# Sheet7.net
KiCad netlist of a schematic drawn in Altium Designer
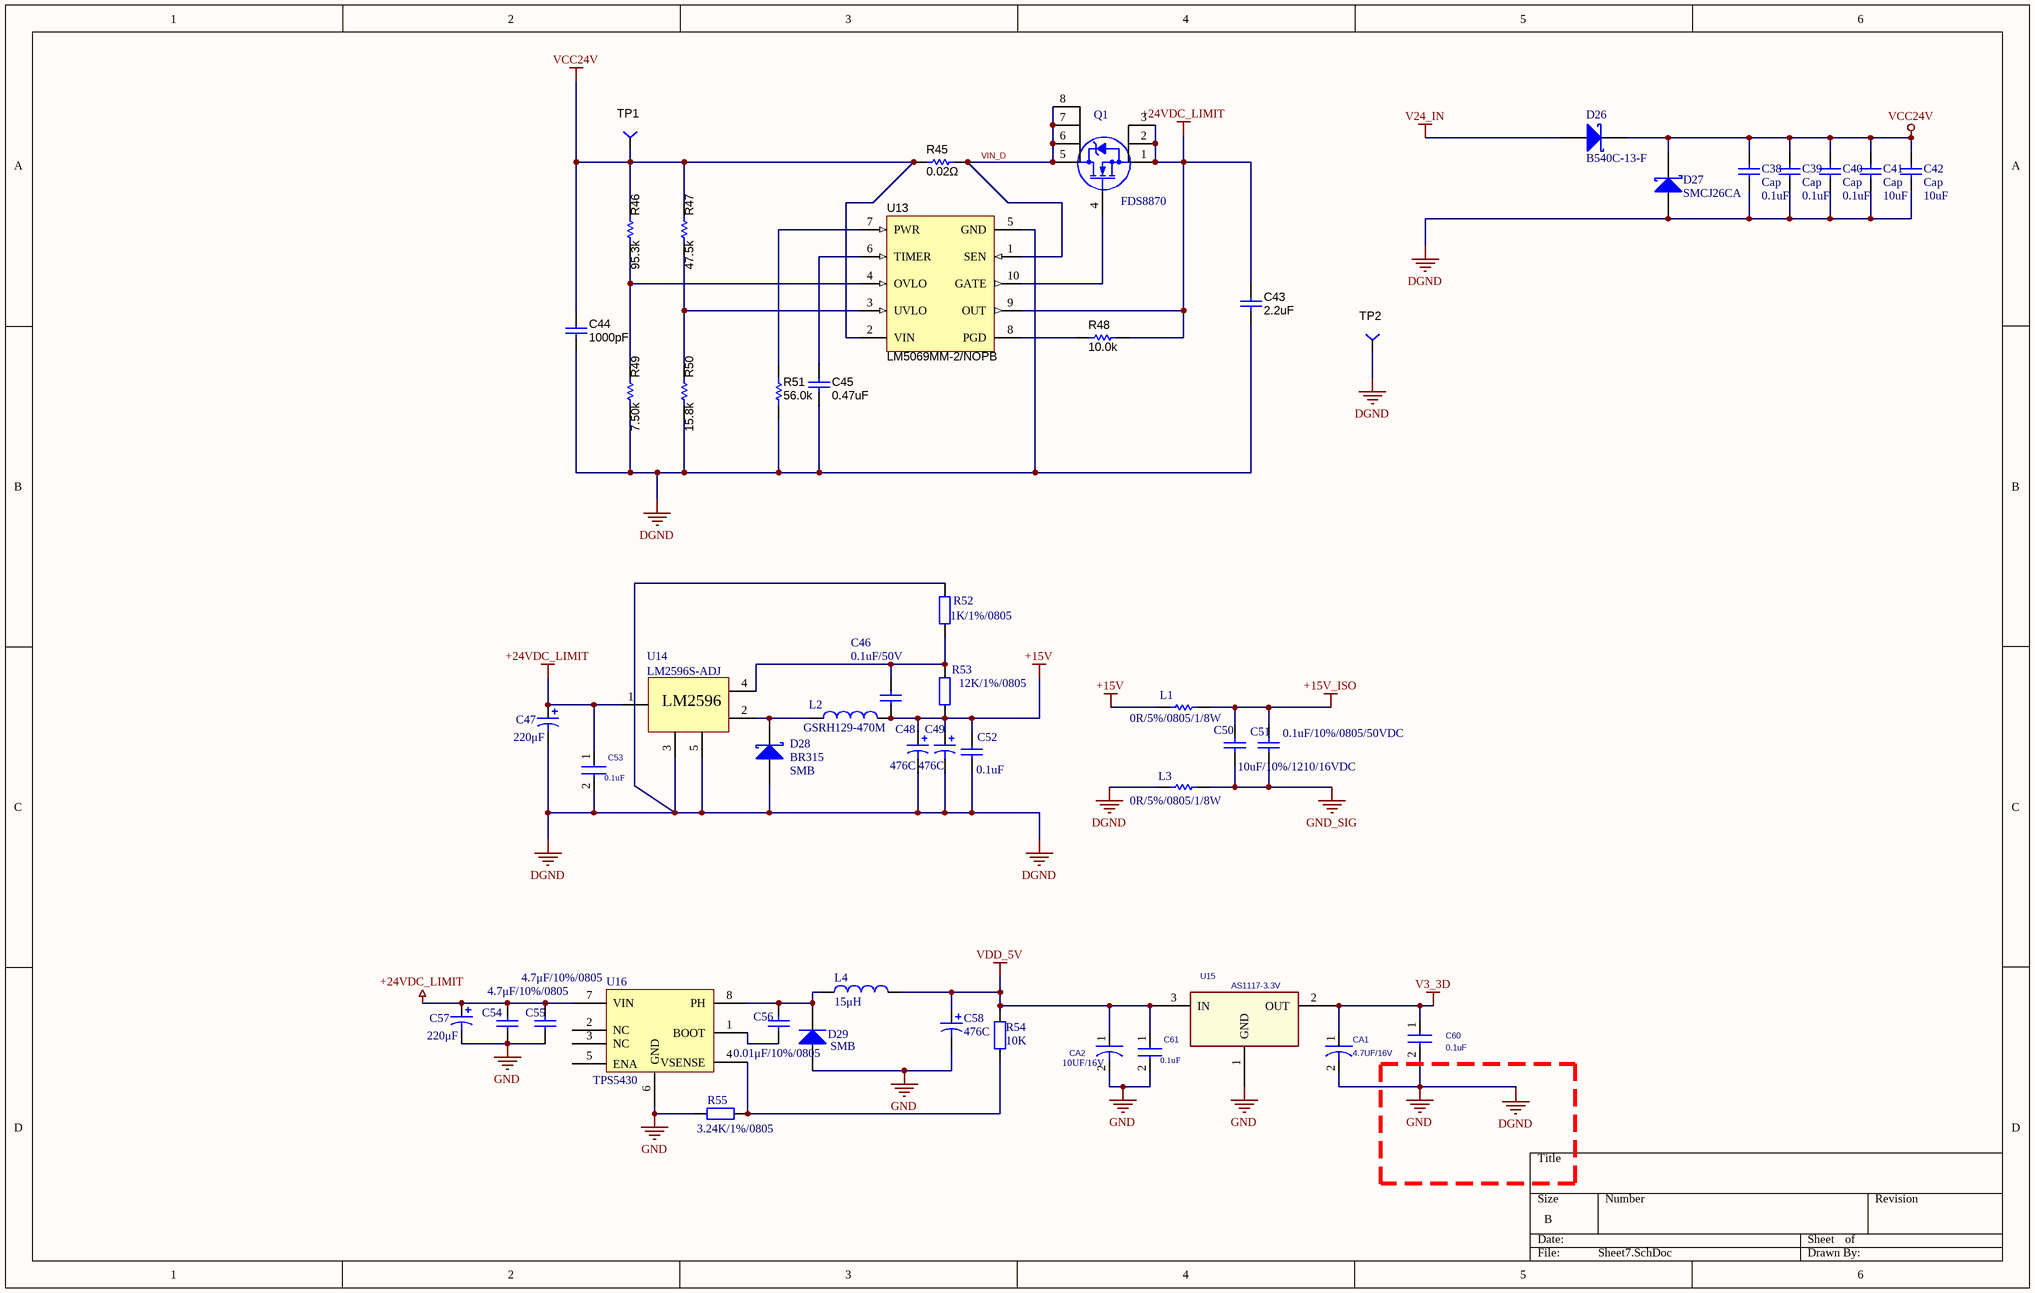
[diagram p0: Sheet7.SchDoc]

(export (version "E")
  (design (tool "Eeschema 10.0.6"))
  (components
    (comp (ref "C38")
      (value "Cap")
      (footprint "0805_cap")
      (description "Capacitor")
      (fields (field (name "ALTIUM_VALUE") "0.1uF") (field (name "PUBLISHER") "Altium Limited"))
      (libsource (lib "Miscellaneous Devices") (part "Cap"))
    )
    (comp (ref "C39")
      (value "Cap")
      (footprint "0805_cap")
      (description "Capacitor")
      (fields (field (name "ALTIUM_VALUE") "0.1uF") (field (name "PUBLISHER") "Altium Limited"))
      (libsource (lib "Miscellaneous Devices") (part "Cap"))
    )
    (comp (ref "C40")
      (value "Cap")
      (footprint "0805_cap")
      (description "Capacitor")
      (fields (field (name "ALTIUM_VALUE") "0.1uF") (field (name "PUBLISHER") "Altium Limited"))
      (libsource (lib "Miscellaneous Devices") (part "Cap"))
    )
    (comp (ref "C41")
      (value "Cap")
      (footprint "0805_cap")
      (description "Capacitor")
      (fields (field (name "ALTIUM_VALUE") "10uF") (field (name "PUBLISHER") "Altium Limited"))
      (libsource (lib "Miscellaneous Devices") (part "Cap"))
    )
    (comp (ref "C42")
      (value "Cap")
      (footprint "0805_cap")
      (description "Capacitor")
      (fields (field (name "ALTIUM_VALUE") "10uF") (field (name "PUBLISHER") "Altium Limited"))
      (libsource (lib "Miscellaneous Devices") (part "Cap"))
    )
    (comp (ref "C43")
      (value "GRM32ER72A225KA35L")
      (footprint "1210")
      (description "CAP, CERM, 2.2uF, 100V, +/-10%, X7R, 1210")
      (fields
        (field (name "VALUEDISPLAYED") "2.2uF")
        (field (name "MANUFACTURER") "MuRata")
        (field (name "PUBLISHER") "Texas Instruments")
      )
      (libsource (lib "Capacitor_Ceramic") (part "GRM32ER72A225KA35L"))
    )
    (comp (ref "C44")
      (value "06031C102JAT2A")
      (footprint "0805_cap")
      (description "CAP, CERM, 1000pF, 100V, +/-5%, X7R, 0603")
      (fields
        (field (name "VALUEDISPLAYED") "1000pF")
        (field (name "MANUFACTURER") "AVX")
        (field (name "PUBLISHER") "Texas Instruments")
      )
      (libsource (lib "Capacitor_Ceramic") (part "06031C102JAT2A"))
    )
    (comp (ref "C45")
      (value "UMK107ABJ474KA-T")
      (footprint "0805_cap")
      (description "CAP, CERM, 0.47uF, 50V, 10%, X5R, 0603")
      (fields
        (field (name "MANUFACTURER") "Taiyo Yuden")
        (field (name "VALUEDISPLAYED") "0.47uF")
        (field (name "PUBLISHER") "Texas Instruments")
      )
      (libsource (lib "TI-INDIA-ALTIUM") (part "UMK107ABJ474KA-T"))
    )
    (comp (ref "C46")
      (value "0.1uF/50V")
      (footprint "C-0805")
      (description "Capacitor")
      (libsource (lib "PCB_Project1_3") (part "Cap"))
    )
    (comp (ref "C47")
      (value "220μF")
      (footprint "CZ3.0/6.5")
      (description "Polarized Capacitor (Radial)")
      (fields (field (name "PUBLISHER") "Altium Limited"))
      (libsource (lib "Miscellaneous Devices") (part "Cap Pol1"))
    )
    (comp (ref "C48")
      (value "476C")
      (footprint "7343-43")
      (description "Polarized Capacitor (Radial)")
      (fields (field (name "PUBLISHER") "Altium Limited"))
      (libsource (lib "Miscellaneous Devices") (part "Cap Pol1"))
    )
    (comp (ref "C49")
      (value "476C")
      (footprint "7343-43")
      (description "Polarized Capacitor (Radial)")
      (fields (field (name "PUBLISHER") "Altium Limited"))
      (libsource (lib "Miscellaneous Devices") (part "Cap Pol1"))
    )
    (comp (ref "C50")
      (value "10uF/10%/1210/16VDC")
      (footprint "C-1210")
      (libsource (lib "浙江关西电机数据库") (part "CAP_Non-polarity"))
    )
    (comp (ref "C51")
      (value "0.1uF/10%/0805/50VDC")
      (footprint "C-0805")
      (libsource (lib "浙江关西电机数据库") (part "CAP_Non-polarity"))
    )
    (comp (ref "C52")
      (value "0.1uF")
      (footprint "C-0805")
      (description "Capacitor")
      (libsource (lib "PCB_Project1_3") (part "Cap"))
    )
    (comp (ref "C53") (value "0.1uF") (footprint "0805_CAP") (libsource (lib "v3") (part "C")))
    (comp (ref "C54")
      (value "4.7μF/10%/0805")
      (footprint "0805_CAP")
      (description "Capacitor")
      (fields (field (name "PUBLISHER") "Altium Limited"))
      (libsource (lib "Miscellaneous Devices") (part "Cap"))
    )
    (comp (ref "C55")
      (value "4.7μF/10%/0805")
      (footprint "0805_CAP")
      (description "Capacitor")
      (fields (field (name "PUBLISHER") "Altium Limited"))
      (libsource (lib "Miscellaneous Devices") (part "Cap"))
    )
    (comp (ref "C56")
      (value "0.01μF/10%/0805")
      (footprint "0805_CAP")
      (description "Capacitor")
      (fields (field (name "PUBLISHER") "Altium Limited"))
      (libsource (lib "Miscellaneous Devices") (part "Cap"))
    )
    (comp (ref "C57")
      (value "220μF")
      (footprint "CZ3.0/6.5")
      (description "Polarized Capacitor (Radial)")
      (fields (field (name "PUBLISHER") "Altium Limited"))
      (libsource (lib "Miscellaneous Devices") (part "Cap Pol1"))
    )
    (comp (ref "C58")
      (value "476C")
      (footprint "7343-43")
      (description "Polarized Capacitor (Radial)")
      (fields (field (name "PUBLISHER") "Altium Limited"))
      (libsource (lib "Miscellaneous Devices") (part "Cap Pol1"))
    )
    (comp (ref "C60") (value "0.1uF") (footprint "0805_CAP") (libsource (lib "v3") (part "C")))
    (comp (ref "C61") (value "0.1uF") (footprint "0805_CAP") (libsource (lib "v3") (part "C")))
    (comp (ref "CA1") (value "4.7UF/16V") (footprint "3528cap") (libsource (lib "v3") (part "ECAP")))
    (comp (ref "CA2") (value "10UF/16V") (footprint "3528cap") (libsource (lib "v3") (part "ECAP")))
    (comp (ref "D26")
      (value "B540C-13-F")
      (footprint "SMB1")
      (description "Schottky Diode")
      (fields (field (name "PUBLISHER") "Altium Limited"))
      (libsource (lib "Miscellaneous Devices") (part "D Schottky"))
    )
    (comp (ref "D27")
      (value "SMCJ26CA")
      (footprint "SMB1")
      (description "Schottky Diode")
      (fields (field (name "PUBLISHER") "Altium Limited"))
      (libsource (lib "Miscellaneous Devices") (part "D Schottky"))
    )
    (comp (ref "D28")
      (value "D Schottky")
      (footprint "SMB")
      (fields (field (name "ALTIUM_UNNAMED_1") "BR315") (field (name "ALTIUM_UNNAMED_2") "SMB"))
      (libsource (lib "SCHLIBRARIES") (part "D Schottky"))
    )
    (comp (ref "D29")
      (value "SMB")
      (footprint "SMB")
      (description "3 Amp Medium Power Silicon Rectifier Diode")
      (fields (field (name "PUBLISHER") "Altium Limited"))
      (libsource (lib "Miscellaneous Devices") (part "Diode 1N5408"))
    )
    (comp (ref "L1")
      (value "0R/5%/0805/1/8W")
      (footprint "R-0805")
      (fields (field (name "PART NUMBER") "ASR-0010AA") (field (name "规格") "0R/5%/0805/1/8W"))
      (libsource (lib "浙江关西电机数据库") (part "RES_1"))
    )
    (comp (ref "L2")
      (value "GSRH129-470M")
      (footprint "GSDS104C2")
      (description "Inductor")
      (libsource (lib "Miscellaneous Devices") (part "Inductor"))
    )
    (comp (ref "L3")
      (value "0R/5%/0805/1/8W")
      (footprint "R-0805")
      (fields (field (name "PART NUMBER") "ASR-0010AA") (field (name "规格") "0R/5%/0805/1/8W"))
      (libsource (lib "浙江关西电机数据库") (part "RES_1"))
    )
    (comp (ref "L4")
      (value "15μH")
      (footprint "GSDS104C2")
      (description "Inductor")
      (fields (field (name "PUBLISHER") "Altium Limited"))
      (libsource (lib "Miscellaneous Devices") (part "Inductor"))
    )
    (comp (ref "Q1")
      (value "FDS8870")
      (footprint "SO-G8")
      (libsource (lib "SCHLIBRARIES") (part "MOSFET_N_8"))
    )
    (comp (ref "R45")
      (value "0.02Ω")
      (footprint "1206")
      (description "RES, 0.02 ohm, 1%, 1W, 1206")
      (fields
        (field (name "PARTNUMBER") "PRL1632-R020-F-T1")
        (field (name "MANUFACTURER") "Susumu Co Ltd")
        (field (name "PUBLISHER") "Texas Instruments")
      )
      (libsource (lib "Resistor_1206") (part "PRL1632-R020-F-T1"))
    )
    (comp (ref "R46")
      (value "95.3k")
      (footprint "0805")
      (description "RES, 95.3k ohm, 1%, 0.1W, 0603")
      (fields
        (field (name "PARTNUMBER") "CRCW060395K3FKEA")
        (field (name "MANUFACTURER") "Vishay-Dale")
        (field (name "PUBLISHER") "Texas Instruments")
      )
      (libsource (lib "Resistor_0603") (part "CRCW060395K3FKEA"))
    )
    (comp (ref "R47")
      (value "47.5k")
      (footprint "0805")
      (description "RES, 47.5k ohm, 1%, 0.1W, 0603")
      (fields
        (field (name "PARTNUMBER") "CRCW060347K5FKEA")
        (field (name "MANUFACTURER") "Vishay-Dale")
        (field (name "PUBLISHER") "Texas Instruments")
      )
      (libsource (lib "Resistor_0603") (part "CRCW060347K5FKEA"))
    )
    (comp (ref "R48")
      (value "10.0k")
      (footprint "0805")
      (description "RES, 10.0k ohm, 1%, 0.1W, 0603")
      (fields
        (field (name "PARTNUMBER") "CRCW060310K0FKEA")
        (field (name "MANUFACTURER") "Vishay-Dale")
        (field (name "PUBLISHER") "Texas Instruments")
      )
      (libsource (lib "Resistor_0603") (part "CRCW060310K0FKEA"))
    )
    (comp (ref "R49")
      (value "7.50k")
      (footprint "0805")
      (description "RES, 7.50k ohm, 1%, 0.1W, 0603")
      (fields
        (field (name "PARTNUMBER") "CRCW06037K50FKEA")
        (field (name "MANUFACTURER") "Vishay-Dale")
        (field (name "PUBLISHER") "Texas Instruments")
      )
      (libsource (lib "Resistor_0603") (part "CRCW06037K50FKEA"))
    )
    (comp (ref "R50")
      (value "15.8k")
      (footprint "0805")
      (description "RES, 15.8k ohm, 1%, 0.1W, 0603")
      (fields
        (field (name "PARTNUMBER") "CRCW060315K8FKEA")
        (field (name "MANUFACTURER") "Vishay-Dale")
        (field (name "PUBLISHER") "Texas Instruments")
      )
      (libsource (lib "Resistor_0603") (part "CRCW060315K8FKEA"))
    )
    (comp (ref "R51")
      (value "56.0k")
      (footprint "0805")
      (description "RES, 56.0k ohm, 0.1%, 0.1W, 0603")
      (fields
        (field (name "PARTNUMBER") "RG1608P-563-B-T5")
        (field (name "MANUFACTURER") "Susumu Co Ltd")
        (field (name "PUBLISHER") "Texas Instruments")
      )
      (libsource (lib "Resistor_0603") (part "RG1608P-563-B-T5"))
    )
    (comp (ref "R52")
      (value "1K/1%/0805")
      (footprint "0805")
      (description "Resistor")
      (fields (field (name "PUBLISHER") "Altium Limited"))
      (libsource (lib "") (part "Res2_1"))
    )
    (comp (ref "R53")
      (value "12K/1%/0805")
      (footprint "0805")
      (description "Resistor")
      (fields (field (name "PUBLISHER") "Altium Limited"))
      (libsource (lib "") (part "Res2_1"))
    )
    (comp (ref "R54")
      (value "10K")
      (footprint "0805")
      (description "Resistor")
      (fields (field (name "PUBLISHER") "Altium Limited"))
      (libsource (lib "") (part "Res2_1"))
    )
    (comp (ref "R55")
      (value "3.24K/1%/0805")
      (footprint "0805")
      (description "Resistor")
      (fields (field (name "PUBLISHER") "Altium Limited"))
      (libsource (lib "Miscellaneous Devices") (part "Res2"))
    )
    (comp (ref "TP1")
      (value "TP-040_RND")
      (footprint "TP-040_RND")
      (description "Test Point, O.040 Hole")
      (fields (field (name "MANUFACTURER") "Standard"))
      (libsource (lib "PADSlegacy_Hardware") (part "TP-040_RND"))
    )
    (comp (ref "TP2")
      (value "TP-040_RND")
      (footprint "TP-040_RND")
      (description "Test Point, O.040 Hole")
      (fields (field (name "MANUFACTURER") "Standard"))
      (libsource (lib "PADSlegacy_Hardware") (part "TP-040_RND"))
    )
    (comp (ref "U13")
      (value "LM5069MM-2/NOPB")
      (footprint "MUB10A_N")
      (fields
        (field (name "MANUFACTURER") "National Semiconductor")
        (field (name "PUBLISHER") "Altium Limited")
      )
      (libsource (lib "NSC MiscPower") (part "LM5069MM-2/NOPB"))
    )
    (comp (ref "U14")
      (value "LM2596S-ADJ")
      (footprint "TO-263(S)-5")
      (libsource (lib "PCB_Project1") (part "SWITCHING"))
    )
    (comp (ref "U15") (value "AS1117-3.3V") (libsource (lib "v3") (part "AS1117")))
    (comp (ref "U16") (value "TPS5430") (footprint "SO-G8") (libsource (lib "SCHLIBRARIES") (part "TPS5430")))
  )
  (nets
    (net (code "1") (name "+15V") (class "Default")
      (node (ref "C46") (pin "2") (pinfunction "2_2") (pintype "passive"))
      (node (ref "C48") (pin "1") (pinfunction "1_1") (pintype "passive"))
      (node (ref "C49") (pin "1") (pinfunction "1_1") (pintype "passive"))
      (node (ref "C52") (pin "2") (pinfunction "2_2") (pintype "passive"))
      (node (ref "L1") (pin "1") (pinfunction "1_1") (pintype "passive"))
      (node (ref "L2") (pin "2") (pinfunction "2_2") (pintype "passive"))
      (node (ref "R53") (pin "1") (pinfunction "1_1") (pintype "passive"))
    )
    (net (code "2") (name "+15V_ISO") (class "Default")
      (node (ref "C50") (pin "2") (pinfunction "2_2") (pintype "passive"))
      (node (ref "C51") (pin "2") (pinfunction "2_2") (pintype "passive"))
      (node (ref "L1") (pin "2") (pinfunction "2_2") (pintype "passive"))
    )
    (net (code "3") (name "+24VDC_LIMIT") (class "Default")
      (node (ref "C43") (pin "1") (pinfunction "1_1") (pintype "passive"))
      (node (ref "C47") (pin "1") (pinfunction "1_1") (pintype "passive"))
      (node (ref "C53") (pin "1") (pinfunction "1_1") (pintype "passive"))
      (node (ref "C54") (pin "2") (pinfunction "2_2") (pintype "passive"))
      (node (ref "C55") (pin "2") (pinfunction "2_2") (pintype "passive"))
      (node (ref "C57") (pin "1") (pinfunction "1_1") (pintype "passive"))
      (node (ref "Q1") (pin "1") (pinfunction "S_1") (pintype "passive"))
      (node (ref "Q1") (pin "2") (pinfunction "S_2") (pintype "passive"))
      (node (ref "Q1") (pin "3") (pinfunction "S_3") (pintype "passive"))
      (node (ref "R48") (pin "1") (pinfunction "1_1") (pintype "passive"))
      (node (ref "U13") (pin "9") (pinfunction "OUT_9") (pintype "output"))
      (node (ref "U14") (pin "1") (pinfunction "1_1") (pintype "passive"))
      (node (ref "U16") (pin "7") (pinfunction "VIN_7") (pintype "passive"))
    )
    (net (code "4") (name "/VIN_D") (class "Default")
      (node (ref "Q1") (pin "5") (pinfunction "D_5") (pintype "passive"))
      (node (ref "Q1") (pin "6") (pinfunction "D_6") (pintype "passive"))
      (node (ref "Q1") (pin "7") (pinfunction "D_7") (pintype "passive"))
      (node (ref "Q1") (pin "8") (pinfunction "D_8") (pintype "passive"))
      (node (ref "R45") (pin "2") (pinfunction "2_2") (pintype "passive"))
      (node (ref "U13") (pin "1") (pinfunction "SEN_1") (pintype "input"))
    )
    (net (code "5") (name "DGND") (class "Default")
      (node (ref "C38") (pin "1") (pinfunction "1_1") (pintype "passive"))
      (node (ref "C39") (pin "1") (pinfunction "1_1") (pintype "passive"))
      (node (ref "C40") (pin "1") (pinfunction "1_1") (pintype "passive"))
      (node (ref "C41") (pin "1") (pinfunction "1_1") (pintype "passive"))
      (node (ref "C42") (pin "1") (pinfunction "1_1") (pintype "passive"))
      (node (ref "C43") (pin "2") (pinfunction "2_2") (pintype "passive"))
      (node (ref "C44") (pin "2") (pinfunction "2_2") (pintype "passive"))
      (node (ref "C45") (pin "2") (pinfunction "2_2") (pintype "passive"))
      (node (ref "C47") (pin "2") (pinfunction "2_2") (pintype "passive"))
      (node (ref "C48") (pin "2") (pinfunction "2_2") (pintype "passive"))
      (node (ref "C49") (pin "2") (pinfunction "2_2") (pintype "passive"))
      (node (ref "C52") (pin "1") (pinfunction "1_1") (pintype "passive"))
      (node (ref "C53") (pin "2") (pinfunction "2_2") (pintype "passive"))
      (node (ref "C54") (pin "1") (pinfunction "1_1") (pintype "passive"))
      (node (ref "C55") (pin "1") (pinfunction "1_1") (pintype "passive"))
      (node (ref "C57") (pin "2") (pinfunction "2_2") (pintype "passive"))
      (node (ref "C58") (pin "2") (pinfunction "2_2") (pintype "passive"))
      (node (ref "C60") (pin "2") (pinfunction "2_2") (pintype "passive"))
      (node (ref "C61") (pin "2") (pinfunction "2_2") (pintype "passive"))
      (node (ref "CA1") (pin "2") (pinfunction "2_2") (pintype "passive"))
      (node (ref "CA2") (pin "2") (pinfunction "2_2") (pintype "passive"))
      (node (ref "D27") (pin "1") (pinfunction "A_1") (pintype "passive"))
      (node (ref "D28") (pin "1") (pinfunction "A_1") (pintype "passive"))
      (node (ref "D29") (pin "1") (pinfunction "A_1") (pintype "passive"))
      (node (ref "L3") (pin "1") (pinfunction "1_1") (pintype "passive"))
      (node (ref "R49") (pin "1") (pinfunction "1_1") (pintype "passive"))
      (node (ref "R50") (pin "1") (pinfunction "1_1") (pintype "passive"))
      (node (ref "R51") (pin "1") (pinfunction "1_1") (pintype "passive"))
      (node (ref "R52") (pin "2") (pinfunction "2_2") (pintype "passive"))
      (node (ref "R55") (pin "2") (pinfunction "2_2") (pintype "passive"))
      (node (ref "TP2") (pin "1") (pinfunction "1_1") (pintype "passive"))
      (node (ref "U13") (pin "5") (pinfunction "GND_5") (pintype "power_in"))
      (node (ref "U14") (pin "3") (pinfunction "3_3") (pintype "passive"))
      (node (ref "U14") (pin "5") (pinfunction "5_5") (pintype "passive"))
      (node (ref "U15") (pin "1") (pinfunction "GND_1") (pintype "passive"))
      (node (ref "U16") (pin "6") (pinfunction "GND_6") (pintype "passive"))
    )
    (net (code "6") (name "GND_SIG") (class "Default")
      (node (ref "C50") (pin "1") (pinfunction "1_1") (pintype "passive"))
      (node (ref "C51") (pin "1") (pinfunction "1_1") (pintype "passive"))
      (node (ref "L3") (pin "2") (pinfunction "2_2") (pintype "passive"))
    )
    (net (code "7") (name "Net-(C46-Pad1)") (class "Default")
      (node (ref "C46") (pin "1") (pinfunction "1_1") (pintype "passive"))
      (node (ref "R52") (pin "1") (pinfunction "1_1") (pintype "passive"))
      (node (ref "R53") (pin "2") (pinfunction "2_2") (pintype "passive"))
      (node (ref "U14") (pin "4") (pinfunction "4_4") (pintype "passive"))
    )
    (net (code "8") (name "Net-(D28-K)") (class "Default")
      (node (ref "D28") (pin "2") (pinfunction "K_2") (pintype "passive"))
      (node (ref "L2") (pin "1") (pinfunction "1_1") (pintype "passive"))
      (node (ref "U14") (pin "2") (pinfunction "2_2") (pintype "passive"))
    )
    (net (code "9") (name "Net-(D29-K)") (class "Default")
      (node (ref "C56") (pin "2") (pinfunction "2_2") (pintype "passive"))
      (node (ref "D29") (pin "2") (pinfunction "K_2") (pintype "passive"))
      (node (ref "L4") (pin "1") (pinfunction "1_1") (pintype "passive"))
      (node (ref "U16") (pin "8") (pinfunction "PH_8") (pintype "passive"))
    )
    (net (code "10") (name "Net-(Q1-G)") (class "Default")
      (node (ref "Q1") (pin "4") (pinfunction "G_4") (pintype "passive"))
      (node (ref "U13") (pin "10") (pinfunction "GATE_10") (pintype "output"))
    )
    (net (code "11") (name "Net-(U13-OVLO)") (class "Default")
      (node (ref "R46") (pin "1") (pinfunction "1_1") (pintype "passive"))
      (node (ref "R49") (pin "2") (pinfunction "2_2") (pintype "passive"))
      (node (ref "U13") (pin "4") (pinfunction "OVLO_4") (pintype "input"))
    )
    (net (code "12") (name "Net-(U13-PGD)") (class "Default")
      (node (ref "R48") (pin "2") (pinfunction "2_2") (pintype "passive"))
      (node (ref "U13") (pin "8") (pinfunction "PGD_8") (pintype "open_collector"))
    )
    (net (code "13") (name "Net-(U13-PWR)") (class "Default")
      (node (ref "R51") (pin "2") (pinfunction "2_2") (pintype "passive"))
      (node (ref "U13") (pin "7") (pinfunction "PWR_7") (pintype "input"))
    )
    (net (code "14") (name "Net-(U13-TIMER)") (class "Default")
      (node (ref "C45") (pin "1") (pinfunction "1_1") (pintype "passive"))
      (node (ref "U13") (pin "6") (pinfunction "TIMER_6") (pintype "input"))
    )
    (net (code "15") (name "Net-(U13-UVLO)") (class "Default")
      (node (ref "R47") (pin "1") (pinfunction "1_1") (pintype "passive"))
      (node (ref "R50") (pin "2") (pinfunction "2_2") (pintype "passive"))
      (node (ref "U13") (pin "3") (pinfunction "UVLO_3") (pintype "input"))
    )
    (net (code "16") (name "Net-(U16-BOOT)") (class "Default")
      (node (ref "C56") (pin "1") (pinfunction "1_1") (pintype "passive"))
      (node (ref "U16") (pin "1") (pinfunction "BOOT_1") (pintype "passive"))
    )
    (net (code "17") (name "Net-(U16-VSENSE)") (class "Default")
      (node (ref "R54") (pin "1") (pinfunction "1_1") (pintype "passive"))
      (node (ref "R55") (pin "1") (pinfunction "1_1") (pintype "passive"))
      (node (ref "U16") (pin "4") (pinfunction "VSENSE_4") (pintype "passive"))
    )
    (net (code "18") (name "V3_3D") (class "Default")
      (node (ref "C60") (pin "1") (pinfunction "1_1") (pintype "passive"))
      (node (ref "CA1") (pin "1") (pinfunction "1_1") (pintype "passive"))
      (node (ref "U15") (pin "2") (pinfunction "OUT_2") (pintype "passive"))
    )
    (net (code "19") (name "V24_IN") (class "Default")
      (node (ref "D26") (pin "1") (pinfunction "A_1") (pintype "passive"))
    )
    (net (code "20") (name "VCC24V") (class "Default")
      (node (ref "C38") (pin "2") (pinfunction "2_2") (pintype "passive"))
      (node (ref "C39") (pin "2") (pinfunction "2_2") (pintype "passive"))
      (node (ref "C40") (pin "2") (pinfunction "2_2") (pintype "passive"))
      (node (ref "C41") (pin "2") (pinfunction "2_2") (pintype "passive"))
      (node (ref "C42") (pin "2") (pinfunction "2_2") (pintype "passive"))
      (node (ref "C44") (pin "1") (pinfunction "1_1") (pintype "passive"))
      (node (ref "D26") (pin "2") (pinfunction "K_2") (pintype "passive"))
      (node (ref "D27") (pin "2") (pinfunction "K_2") (pintype "passive"))
      (node (ref "R45") (pin "1") (pinfunction "1_1") (pintype "passive"))
      (node (ref "R46") (pin "2") (pinfunction "2_2") (pintype "passive"))
      (node (ref "R47") (pin "2") (pinfunction "2_2") (pintype "passive"))
      (node (ref "TP1") (pin "1") (pinfunction "1_1") (pintype "passive"))
      (node (ref "U13") (pin "2") (pinfunction "VIN_2") (pintype "power_in"))
    )
    (net (code "21") (name "VDD_5V") (class "Default")
      (node (ref "C58") (pin "1") (pinfunction "1_1") (pintype "passive"))
      (node (ref "C61") (pin "1") (pinfunction "1_1") (pintype "passive"))
      (node (ref "CA2") (pin "1") (pinfunction "1_1") (pintype "passive"))
      (node (ref "L4") (pin "2") (pinfunction "2_2") (pintype "passive"))
      (node (ref "R54") (pin "2") (pinfunction "2_2") (pintype "passive"))
      (node (ref "U15") (pin "3") (pinfunction "IN_3") (pintype "passive"))
    )
    (net (code "22") (name "unconnected-(U16-ENA-Pad5)") (class "Default")
      (node (ref "U16") (pin "5") (pinfunction "ENA_5") (pintype "passive"))
    )
    (net (code "23") (name "unconnected-(U16-NC-Pad2)") (class "Default")
      (node (ref "U16") (pin "2") (pinfunction "NC_2") (pintype "passive"))
    )
    (net (code "24") (name "unconnected-(U16-NC-Pad3)") (class "Default")
      (node (ref "U16") (pin "3") (pinfunction "NC_3") (pintype "passive"))
    )
  )
)
